# v1_0.net
KiCad netlist of a schematic drawn in Altium Designer
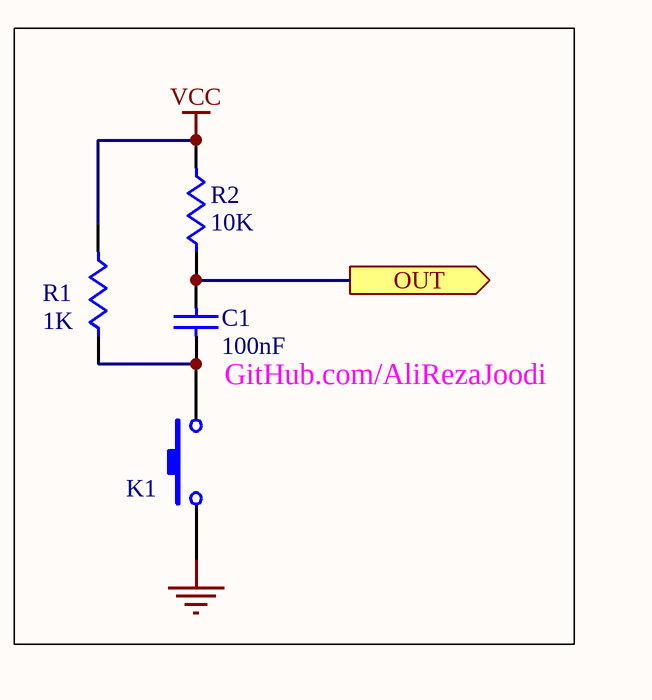
[diagram p0: v1.0.SchDoc]

(export (version "E")
  (design (tool "Eeschema 10.0.6"))
  (components
    (comp (ref "C1")
      (value "100nF")
      (footprint "CAPNTO2.54-3.56x2.03")
      (description "Capacitor")
      (fields (field (name "MANUFACTURER") "Generic Components") (field (name "PUBLISHER") "Altium Limited"))
      (libsource (lib "Miscellaneous Devices") (part "Cap"))
    )
    (comp (ref "K1")
      (value "SW-PB")
      (footprint "SPST-2_2")
      (description "Switch")
      (fields (field (name "MANUFACTURER") "Generic Components") (field (name "PUBLISHER") "Altium Limited"))
      (libsource (lib "Miscellaneous Devices") (part "SW-PB"))
    )
    (comp (ref "R1")
      (value "1K")
      (footprint "AXIAL-0.4")
      (description "Resistor")
      (fields (field (name "MANUFACTURER") "Generic Components") (field (name "PUBLISHER") "Altium Limited"))
      (libsource (lib "Miscellaneous Devices") (part "Res1"))
    )
    (comp (ref "R2")
      (value "10K")
      (footprint "AXIAL-0.4")
      (description "Resistor")
      (fields (field (name "MANUFACTURER") "Generic Components") (field (name "PUBLISHER") "Altium Limited"))
      (libsource (lib "Miscellaneous Devices") (part "Res1"))
    )
  )
  (nets
    (net (code "1") (name "/OUT") (class "Default")
      (node (ref "C1") (pin "1") (pinfunction "1_1") (pintype "passive"))
      (node (ref "R2") (pin "1") (pinfunction "1_1") (pintype "passive"))
    )
    (net (code "2") (name "GND") (class "Default")
      (node (ref "K1") (pin "1") (pinfunction "1_1") (pintype "passive"))
    )
    (net (code "3") (name "Net-(C1-Pad2)") (class "Default")
      (node (ref "C1") (pin "2") (pinfunction "2_2") (pintype "passive"))
      (node (ref "K1") (pin "2") (pinfunction "2_2") (pintype "passive"))
      (node (ref "R1") (pin "1") (pinfunction "1_1") (pintype "passive"))
    )
    (net (code "4") (name "VCC") (class "Default")
      (node (ref "R1") (pin "2") (pinfunction "2_2") (pintype "passive"))
      (node (ref "R2") (pin "2") (pinfunction "2_2") (pintype "passive"))
    )
  )
)
